# CH32V307VCT6-R0.net
KiCad netlist of a schematic drawn in Altium Designer
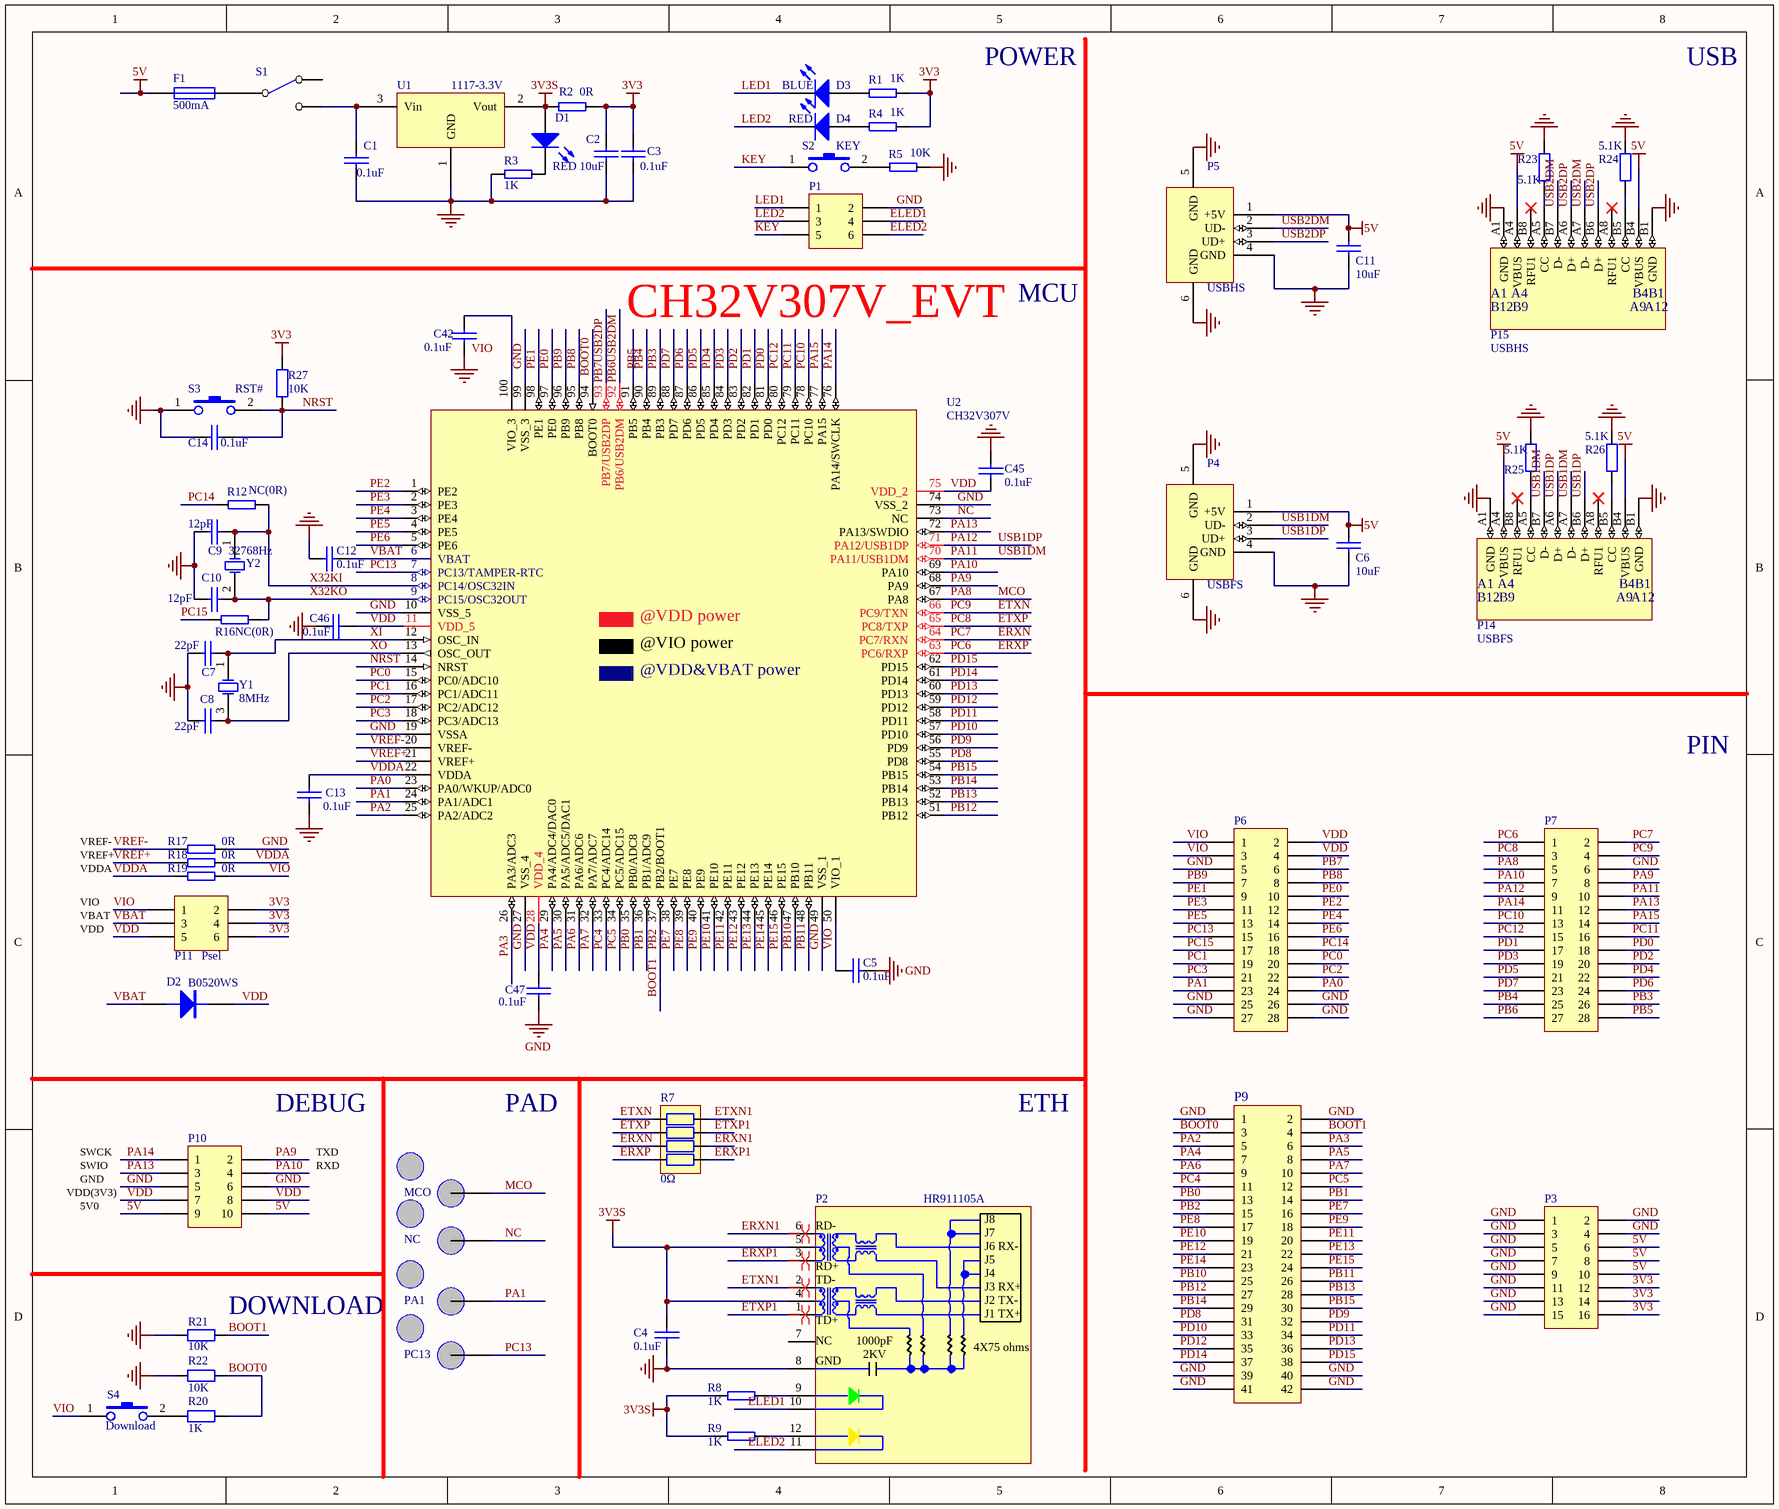
[diagram p0: CH32V307VCT6-R0.SchDoc]

(export (version "E")
  (design (tool "Eeschema 10.0.6"))
  (components
    (comp (ref "C1")
      (value "0.1uF")
      (footprint "0603_C")
      (description "Capacitor")
      (libsource (lib "") (part "CAP_1"))
    )
    (comp (ref "C2")
      (value "10uF")
      (footprint "3216_C")
      (description "Capacitor")
      (libsource (lib "") (part "CAP_1"))
    )
    (comp (ref "C3")
      (value "0.1uF")
      (footprint "0603_C")
      (description "Capacitor")
      (libsource (lib "") (part "CAP_1"))
    )
    (comp (ref "C4")
      (value "0.1uF")
      (footprint "0603_C")
      (description "Capacitor")
      (libsource (lib "") (part "CAP_1"))
    )
    (comp (ref "C5")
      (value "0.1uF")
      (footprint "0603_C")
      (description "Capacitor")
      (libsource (lib "") (part "CAP_1"))
    )
    (comp (ref "C6")
      (value "10uF")
      (footprint "3216_C")
      (description "Capacitor")
      (libsource (lib "*") (part "CAP"))
    )
    (comp (ref "C7")
      (value "22pF")
      (footprint "0603_C")
      (description "Capacitor")
      (libsource (lib "") (part "CAP_1"))
    )
    (comp (ref "C8")
      (value "22pF")
      (footprint "0603_C")
      (description "Capacitor")
      (libsource (lib "") (part "CAP_1"))
    )
    (comp (ref "C9")
      (value "12pF")
      (footprint "0603_C")
      (description "Capacitor")
      (libsource (lib "") (part "CAP_1"))
    )
    (comp (ref "C10")
      (value "12pF")
      (footprint "0603_C")
      (description "Capacitor")
      (libsource (lib "") (part "CAP_1"))
    )
    (comp (ref "C11")
      (value "10uF")
      (footprint "3216_C")
      (description "Capacitor")
      (libsource (lib "*") (part "CAP"))
    )
    (comp (ref "C12")
      (value "0.1uF")
      (footprint "0603_C")
      (description "Capacitor")
      (libsource (lib "") (part "CAP_1"))
    )
    (comp (ref "C13")
      (value "0.1uF")
      (footprint "0603_C")
      (description "Capacitor")
      (libsource (lib "") (part "CAP_1"))
    )
    (comp (ref "C14")
      (value "0.1uF")
      (footprint "0603_C")
      (description "Capacitor")
      (libsource (lib "*") (part "CAP"))
    )
    (comp (ref "C42")
      (value "0.1uF")
      (footprint "0603_C")
      (description "Capacitor")
      (libsource (lib "") (part "CAP_1"))
    )
    (comp (ref "C45")
      (value "0.1uF")
      (footprint "0603_C")
      (description "Capacitor")
      (libsource (lib "") (part "CAP_1"))
    )
    (comp (ref "C46")
      (value "0.1uF")
      (footprint "0603_C")
      (description "Capacitor")
      (libsource (lib "") (part "CAP_1"))
    )
    (comp (ref "C47")
      (value "0.1uF")
      (footprint "0603_C")
      (description "Capacitor")
      (libsource (lib "") (part "CAP_1"))
    )
    (comp (ref "D1")
      (value "RED")
      (footprint "0603+")
      (description "Typical INFRARED GaAs LED")
      (fields (field (name "PUBLISHER") "Altium Limited"))
      (libsource (lib "*") (part "LED0"))
    )
    (comp (ref "D2")
      (value "B0520WS")
      (footprint "SOD-323")
      (description "Diode")
      (libsource (lib "*") (part "DIODE"))
    )
    (comp (ref "D3")
      (value "BLUE")
      (footprint "0603+")
      (description "Typical INFRARED GaAs LED")
      (fields (field (name "PUBLISHER") "Altium Limited"))
      (libsource (lib "*") (part "LED0"))
    )
    (comp (ref "D4")
      (value "RED")
      (footprint "0603+")
      (description "Typical INFRARED GaAs LED")
      (fields (field (name "PUBLISHER") "Altium Limited"))
      (libsource (lib "*") (part "LED0"))
    )
    (comp (ref "F1")
      (value "500mA")
      (footprint "0805")
      (description "Fuse")
      (libsource (lib "wch_sch_others") (part "FUSE1"))
    )
    (comp (ref "MCO")
      (value "Testpoint")
      (footprint "TESTPOINT1")
      (description "测试点")
      (libsource (lib "wch_sch_others") (part "Testpoint"))
    )
    (comp (ref "NC")
      (value "Testpoint")
      (footprint "TESTPOINT1")
      (description "测试点")
      (libsource (lib "wch_sch_others") (part "Testpoint"))
    )
    (comp (ref "P1")
      (value "IO")
      (footprint "IDC6-2.54mm")
      (description "Header, 3-Pin, Dual row, Right Angle")
      (fields (field (name "PUBLISHER") "Altium Limited"))
      (libsource (lib "Miscellaneous Connectors") (part "Header 3X2H"))
    )
    (comp (ref "P2") (value "HR911105A") (footprint "HR911105A") (libsource (lib "*") (part "HR911105A")))
    (comp (ref "P3")
      (value "Ppin")
      (footprint "IDC16-2.54mm")
      (description "Header, 8-Pin, Dual row, Right Angle")
      (fields (field (name "PUBLISHER") "Altium Limited"))
      (libsource (lib "Miscellaneous Connectors") (part "Header 8X2H"))
    )
    (comp (ref "P4")
      (value "USBFS")
      (footprint "USBAF")
      (description "USB Port")
      (libsource (lib "*") (part "USB"))
    )
    (comp (ref "P5")
      (value "USBHS")
      (footprint "USBAF")
      (description "USB Port")
      (libsource (lib "*") (part "USB"))
    )
    (comp (ref "P6")
      (value "HEADER 14x2")
      (footprint "MYPCB:IDC28-2.54MM")
      (description "Header, 14-Pin, Dual row")
      (libsource (lib "wch_sch_others") (part "HEADER 14x2"))
    )
    (comp (ref "P7")
      (value "HEADER 14x2")
      (footprint "MYPCB:IDC28-2.54MM")
      (description "Header, 14-Pin, Dual row")
      (libsource (lib "wch_sch_others") (part "HEADER 14x2"))
    )
    (comp (ref "P9")
      (value "HEADER 21x2")
      (footprint "MYPCB:IDC42-2.54MM")
      (description "Header, 21-Pin, Dual row")
      (libsource (lib "wch_sch_others") (part "HEADER 21x2"))
    )
    (comp (ref "P10")
      (value "LINK")
      (footprint "IDC10-2.54mm")
      (description "Header, 5-Pin, Dual row, Right Angle")
      (fields (field (name "PUBLISHER") "Altium Limited"))
      (libsource (lib "Miscellaneous Connectors") (part "Header 5X2H"))
    )
    (comp (ref "P11")
      (value "Psel")
      (footprint "IDC6-2.54mm")
      (description "Header, 3-Pin, Dual row, Right Angle")
      (fields (field (name "PUBLISHER") "Altium Limited"))
      (libsource (lib "Miscellaneous Connectors") (part "Header 3X2H"))
    )
    (comp (ref "P14")
      (value "USBFS")
      (footprint "TYPE-C-Receptacle-2.0")
      (libsource (lib "*") (part "TYPE-C1"))
    )
    (comp (ref "P15")
      (value "USBHS")
      (footprint "TYPE-C-Receptacle-2.0")
      (libsource (lib "*") (part "TYPE-C1"))
    )
    (comp (ref "PA1")
      (value "Testpoint")
      (footprint "TESTPOINT1")
      (description "测试点")
      (libsource (lib "wch_sch_others") (part "Testpoint"))
    )
    (comp (ref "PC13")
      (value "Testpoint")
      (footprint "TESTPOINT1")
      (description "测试点")
      (libsource (lib "wch_sch_others") (part "Testpoint"))
    )
    (comp (ref "R1") (value "1K") (footprint "0603") (libsource (lib "wch_sch_others") (part "RES")))
    (comp (ref "R2") (value "0R") (footprint "0603") (libsource (lib "wch_sch_others") (part "RES")))
    (comp (ref "R3") (value "1K") (footprint "0603") (libsource (lib "wch_sch_others") (part "RES")))
    (comp (ref "R4") (value "1K") (footprint "0603") (libsource (lib "wch_sch_others") (part "RES")))
    (comp (ref "R5") (value "10K") (footprint "0603") (libsource (lib "wch_sch_others") (part "RES")))
    (comp (ref "R7")
      (value "0Ω")
      (footprint "RCA-8P4R-0603")
      (description "贴片网络排阻")
      (fields (field (name "版权归属") "源创客"))
      (libsource (lib "wch_sch_others") (part "R-8P4R"))
    )
    (comp (ref "R8") (value "1K") (footprint "0603") (libsource (lib "wch_sch_others") (part "RES")))
    (comp (ref "R9") (value "1K") (footprint "0603") (libsource (lib "wch_sch_others") (part "RES")))
    (comp (ref "R12") (value "NC(0R)") (footprint "0603") (libsource (lib "wch_sch_others") (part "RES")))
    (comp (ref "R16") (value "NC(0R)") (footprint "0603") (libsource (lib "wch_sch_others") (part "RES")))
    (comp (ref "R17") (value "0R") (footprint "0603") (libsource (lib "*") (part "R")))
    (comp (ref "R18") (value "0R") (footprint "0603") (libsource (lib "*") (part "R")))
    (comp (ref "R19") (value "0R") (footprint "0603") (libsource (lib "*") (part "R")))
    (comp (ref "R20")
      (value "1K")
      (footprint "0603")
      (description "Resistor")
      (fields (field (name "PUBLISHER") "Altium Limited"))
      (libsource (lib "Miscellaneous Devices") (part "Res2"))
    )
    (comp (ref "R21")
      (value "10K")
      (footprint "0603")
      (description "Resistor")
      (fields (field (name "PUBLISHER") "Altium Limited"))
      (libsource (lib "Miscellaneous Devices") (part "Res2"))
    )
    (comp (ref "R22")
      (value "10K")
      (footprint "0603")
      (description "Resistor")
      (fields (field (name "PUBLISHER") "Altium Limited"))
      (libsource (lib "Miscellaneous Devices") (part "Res2"))
    )
    (comp (ref "R23")
      (value "5.1K")
      (footprint "0603")
      (description "Resistor")
      (libsource (lib "") (part "Res2_1"))
    )
    (comp (ref "R24")
      (value "5.1K")
      (footprint "0603")
      (description "Resistor")
      (libsource (lib "") (part "Res2_1"))
    )
    (comp (ref "R25")
      (value "5.1K")
      (footprint "0603")
      (description "Resistor")
      (libsource (lib "") (part "Res2_1"))
    )
    (comp (ref "R26")
      (value "5.1K")
      (footprint "0603")
      (description "Resistor")
      (libsource (lib "") (part "Res2_1"))
    )
    (comp (ref "R27")
      (value "10K")
      (footprint "0603")
      (description "Resistor")
      (fields (field (name "PUBLISHER") "Altium Limited"))
      (libsource (lib "") (part "Res2_1"))
    )
    (comp (ref "S1") (value "SW SPDT") (footprint "KEY_B") (libsource (lib "*") (part "SW SPDT")))
    (comp (ref "S2")
      (value "KEY")
      (footprint "SMD_6.1x3.65x2.5mm-KEY")
      (libsource (lib "wch_sch_others") (part "KEY1"))
    )
    (comp (ref "S3")
      (value "RST#")
      (footprint "SMD_6.1x3.65x2.5mm-KEY")
      (libsource (lib "wch_sch_others") (part "KEY1"))
    )
    (comp (ref "S4")
      (value "Download")
      (footprint "SMD_6.1x3.65x2.5mm-KEY")
      (libsource (lib "wch_sch_others") (part "KEY1"))
    )
    (comp (ref "U1")
      (value "1117-3.3V")
      (footprint "SOT-223")
      (libsource (lib "wch_sch_others") (part "1117-3.3V"))
    )
    (comp (ref "U2")
      (value "CH32V307V")
      (footprint "LQFP100")
      (description "RISC-V FPU HD-MCU, 144MHz, USB_480M, USB OTG, 1000M Ethernet MAC, 2*CAN, FSMC+DVP")
      (libsource (lib "CHXXX") (part "CH32V307V"))
    )
    (comp (ref "Y1")
      (value "8MHz")
      (footprint "XT3225")
      (description "Crystal Oscillator")
      (fields (field (name "PUBLISHER") "Altium Limited"))
      (libsource (lib "*") (part "XTAL"))
    )
    (comp (ref "Y2")
      (value "32768Hz")
      (footprint "FC-135")
      (description "Crystal Oscillator")
      (fields (field (name "PUBLISHER") "Altium Limited"))
      (libsource (lib "") (part "XTAL_1"))
    )
  )
  (nets
    (net (code "2") (name "/BOOT0") (class "Default")
      (node (ref "P9") (pin "3") (pinfunction "3_3") (pintype "passive"))
      (node (ref "R20") (pin "1") (pinfunction "1_1") (pintype "passive"))
      (node (ref "R22") (pin "1") (pinfunction "1_1") (pintype "passive"))
      (node (ref "U2") (pin "94") (pinfunction "BOOT0_94") (pintype "input"))
    )
    (net (code "3") (name "/BOOT1") (class "Default")
      (node (ref "P9") (pin "15") (pinfunction "15_15") (pintype "passive"))
      (node (ref "P9") (pin "4") (pinfunction "4_4") (pintype "passive"))
      (node (ref "R21") (pin "1") (pinfunction "1_1") (pintype "passive"))
      (node (ref "U2") (pin "37") (pinfunction "PB2/BOOT1_37") (pintype "bidirectional"))
    )
    (net (code "4") (name "/ELED1") (class "Default")
      (node (ref "P1") (pin "4") (pinfunction "4_4") (pintype "passive"))
      (node (ref "P2") (pin "10") (pintype "passive"))
    )
    (net (code "5") (name "/ELED2") (class "Default")
      (node (ref "P1") (pin "6") (pinfunction "6_6") (pintype "passive"))
      (node (ref "P2") (pin "11") (pintype "passive"))
    )
    (net (code "6") (name "/ERXN") (class "Default")
      (node (ref "P7") (pin "2") (pinfunction "2_2") (pintype "passive"))
      (node (ref "R7") (pin "3") (pinfunction "3_3") (pintype "passive"))
      (node (ref "U2") (pin "64") (pinfunction "PC7/RXN_64") (pintype "bidirectional"))
    )
    (net (code "7") (name "/ERXN1") (class "Default")
      (node (ref "P2") (pin "6") (pintype "passive"))
      (node (ref "R7") (pin "6") (pinfunction "6_6") (pintype "passive"))
    )
    (net (code "8") (name "/ERXP") (class "Default")
      (node (ref "P7") (pin "1") (pinfunction "1_1") (pintype "passive"))
      (node (ref "R7") (pin "4") (pinfunction "4_4") (pintype "passive"))
      (node (ref "U2") (pin "63") (pinfunction "PC6/RXP_63") (pintype "bidirectional"))
    )
    (net (code "9") (name "/ERXP1") (class "Default")
      (node (ref "P2") (pin "3") (pintype "passive"))
      (node (ref "R7") (pin "5") (pinfunction "5_5") (pintype "passive"))
    )
    (net (code "10") (name "/ETXN") (class "Default")
      (node (ref "P7") (pin "4") (pinfunction "4_4") (pintype "passive"))
      (node (ref "R7") (pin "1") (pinfunction "1_1") (pintype "passive"))
      (node (ref "U2") (pin "66") (pinfunction "PC9/TXN_66") (pintype "bidirectional"))
    )
    (net (code "11") (name "/ETXN1") (class "Default")
      (node (ref "P2") (pin "2") (pintype "passive"))
      (node (ref "R7") (pin "8") (pinfunction "8_8") (pintype "passive"))
    )
    (net (code "12") (name "/ETXP") (class "Default")
      (node (ref "P7") (pin "3") (pinfunction "3_3") (pintype "passive"))
      (node (ref "R7") (pin "2") (pinfunction "2_2") (pintype "passive"))
      (node (ref "U2") (pin "65") (pinfunction "PC8/TXP_65") (pintype "bidirectional"))
    )
    (net (code "13") (name "/ETXP1") (class "Default")
      (node (ref "P2") (pin "1") (pintype "passive"))
      (node (ref "R7") (pin "7") (pinfunction "7_7") (pintype "passive"))
    )
    (net (code "14") (name "/KEY") (class "Default")
      (node (ref "P1") (pin "5") (pinfunction "5_5") (pintype "passive"))
      (node (ref "S2") (pin "1") (pinfunction "1_1") (pintype "passive"))
    )
    (net (code "15") (name "/LED1") (class "Default")
      (node (ref "D3") (pin "2") (pinfunction "K_2") (pintype "passive"))
      (node (ref "P1") (pin "1") (pinfunction "1_1") (pintype "passive"))
    )
    (net (code "16") (name "/LED2") (class "Default")
      (node (ref "D4") (pin "2") (pinfunction "K_2") (pintype "passive"))
      (node (ref "P1") (pin "3") (pinfunction "3_3") (pintype "passive"))
    )
    (net (code "17") (name "/MCO") (class "Default")
      (node (ref "MCO") (pin "1") (pinfunction "point_1") (pintype "passive"))
      (node (ref "P7") (pin "5") (pinfunction "5_5") (pintype "passive"))
      (node (ref "U2") (pin "67") (pinfunction "PA8_67") (pintype "bidirectional"))
    )
    (net (code "18") (name "/NC") (class "Default")
      (node (ref "NC") (pin "1") (pinfunction "point_1") (pintype "passive"))
      (node (ref "U2") (pin "73") (pinfunction "NC_73") (pintype "tri_state"))
    )
    (net (code "19") (name "/NRST") (class "Default")
      (node (ref "C14") (pin "2") (pinfunction "2_2") (pintype "passive"))
      (node (ref "R27") (pin "1") (pinfunction "1_1") (pintype "passive"))
      (node (ref "S3") (pin "2") (pinfunction "2_2") (pintype "passive"))
      (node (ref "U2") (pin "14") (pinfunction "NRST_14") (pintype "input"))
    )
    (net (code "20") (name "/PA0") (class "Default")
      (node (ref "P6") (pin "24") (pinfunction "24_24") (pintype "passive"))
      (node (ref "U2") (pin "23") (pinfunction "PA0/WKUP/ADC0_23") (pintype "bidirectional"))
    )
    (net (code "21") (name "/PA1") (class "Default")
      (node (ref "P6") (pin "23") (pinfunction "23_23") (pintype "passive"))
      (node (ref "PA1") (pin "1") (pinfunction "point_1") (pintype "passive"))
      (node (ref "U2") (pin "24") (pinfunction "PA1/ADC1_24") (pintype "bidirectional"))
    )
    (net (code "22") (name "/PA2") (class "Default")
      (node (ref "P9") (pin "5") (pinfunction "5_5") (pintype "passive"))
      (node (ref "U2") (pin "25") (pinfunction "PA2/ADC2_25") (pintype "bidirectional"))
    )
    (net (code "23") (name "/PA3") (class "Default")
      (node (ref "P9") (pin "6") (pinfunction "6_6") (pintype "passive"))
      (node (ref "U2") (pin "26") (pinfunction "PA3/ADC3_26") (pintype "bidirectional"))
    )
    (net (code "24") (name "/PA4") (class "Default")
      (node (ref "P9") (pin "7") (pinfunction "7_7") (pintype "passive"))
      (node (ref "U2") (pin "29") (pinfunction "PA4/ADC4/DAC0_29") (pintype "bidirectional"))
    )
    (net (code "25") (name "/PA5") (class "Default")
      (node (ref "P9") (pin "8") (pinfunction "8_8") (pintype "passive"))
      (node (ref "U2") (pin "30") (pinfunction "PA5/ADC5/DAC1_30") (pintype "bidirectional"))
    )
    (net (code "26") (name "/PA6") (class "Default")
      (node (ref "P9") (pin "9") (pinfunction "9_9") (pintype "passive"))
      (node (ref "U2") (pin "31") (pinfunction "PA6/ADC6_31") (pintype "bidirectional"))
    )
    (net (code "27") (name "/PA7") (class "Default")
      (node (ref "P9") (pin "10") (pinfunction "10_10") (pintype "passive"))
      (node (ref "U2") (pin "32") (pinfunction "PA7/ADC7_32") (pintype "bidirectional"))
    )
    (net (code "28") (name "/PA9") (class "Default")
      (node (ref "P10") (pin "2") (pinfunction "2_2") (pintype "passive"))
      (node (ref "P7") (pin "8") (pinfunction "8_8") (pintype "passive"))
      (node (ref "U2") (pin "68") (pinfunction "PA9_68") (pintype "bidirectional"))
    )
    (net (code "29") (name "/PA10") (class "Default")
      (node (ref "P10") (pin "4") (pinfunction "4_4") (pintype "passive"))
      (node (ref "P7") (pin "7") (pinfunction "7_7") (pintype "passive"))
      (node (ref "U2") (pin "69") (pinfunction "PA10_69") (pintype "bidirectional"))
    )
    (net (code "30") (name "/PA11") (class "Default")
      (node (ref "P14") (pin "A7") (pinfunction "D-_A7") (pintype "bidirectional"))
      (node (ref "P14") (pin "B7") (pinfunction "D-_B7") (pintype "bidirectional"))
      (node (ref "P4") (pin "2") (pinfunction "UD-_2") (pintype "bidirectional"))
      (node (ref "P7") (pin "10") (pinfunction "10_10") (pintype "passive"))
      (node (ref "U2") (pin "70") (pinfunction "PA11/USB1DM_70") (pintype "bidirectional"))
    )
    (net (code "31") (name "/PA12") (class "Default")
      (node (ref "P14") (pin "A6") (pinfunction "D+_A6") (pintype "bidirectional"))
      (node (ref "P14") (pin "B6") (pinfunction "D+_B6") (pintype "bidirectional"))
      (node (ref "P4") (pin "3") (pinfunction "UD+_3") (pintype "bidirectional"))
      (node (ref "P7") (pin "9") (pinfunction "9_9") (pintype "passive"))
      (node (ref "U2") (pin "71") (pinfunction "PA12/USB1DP_71") (pintype "bidirectional"))
    )
    (net (code "32") (name "/PA13") (class "Default")
      (node (ref "P10") (pin "3") (pinfunction "3_3") (pintype "passive"))
      (node (ref "P7") (pin "12") (pinfunction "12_12") (pintype "passive"))
      (node (ref "U2") (pin "72") (pinfunction "PA13/SWDIO_72") (pintype "bidirectional"))
    )
    (net (code "33") (name "/PA14") (class "Default")
      (node (ref "P10") (pin "1") (pinfunction "1_1") (pintype "passive"))
      (node (ref "P7") (pin "11") (pinfunction "11_11") (pintype "passive"))
      (node (ref "U2") (pin "76") (pinfunction "PA14/SWCLK_76") (pintype "bidirectional"))
    )
    (net (code "34") (name "/PA15") (class "Default")
      (node (ref "P7") (pin "14") (pinfunction "14_14") (pintype "passive"))
      (node (ref "U2") (pin "77") (pinfunction "PA15_77") (pintype "bidirectional"))
    )
    (net (code "35") (name "/PB0") (class "Default")
      (node (ref "P9") (pin "13") (pinfunction "13_13") (pintype "passive"))
      (node (ref "U2") (pin "35") (pinfunction "PB0/ADC8_35") (pintype "bidirectional"))
    )
    (net (code "36") (name "/PB1") (class "Default")
      (node (ref "P9") (pin "14") (pinfunction "14_14") (pintype "passive"))
      (node (ref "U2") (pin "36") (pinfunction "PB1/ADC9_36") (pintype "bidirectional"))
    )
    (net (code "37") (name "/PB3") (class "Default")
      (node (ref "P7") (pin "26") (pinfunction "26_26") (pintype "passive"))
      (node (ref "U2") (pin "89") (pinfunction "PB3_89") (pintype "bidirectional"))
    )
    (net (code "38") (name "/PB4") (class "Default")
      (node (ref "P7") (pin "25") (pinfunction "25_25") (pintype "passive"))
      (node (ref "U2") (pin "90") (pinfunction "PB4_90") (pintype "bidirectional"))
    )
    (net (code "39") (name "/PB5") (class "Default")
      (node (ref "P7") (pin "28") (pinfunction "28_28") (pintype "passive"))
    )
    (net (code "40") (name "/PB6") (class "Default")
      (node (ref "P15") (pin "A7") (pinfunction "D-_A7") (pintype "bidirectional"))
      (node (ref "P15") (pin "B7") (pinfunction "D-_B7") (pintype "bidirectional"))
      (node (ref "P5") (pin "2") (pinfunction "UD-_2") (pintype "bidirectional"))
      (node (ref "P7") (pin "27") (pinfunction "27_27") (pintype "passive"))
      (node (ref "U2") (pin "92") (pinfunction "PB6/USB2DM_92") (pintype "bidirectional"))
    )
    (net (code "41") (name "/PB7") (class "Default")
      (node (ref "P15") (pin "A6") (pinfunction "D+_A6") (pintype "bidirectional"))
      (node (ref "P15") (pin "B6") (pinfunction "D+_B6") (pintype "bidirectional"))
      (node (ref "P5") (pin "3") (pinfunction "UD+_3") (pintype "bidirectional"))
      (node (ref "P6") (pin "6") (pinfunction "6_6") (pintype "passive"))
      (node (ref "U2") (pin "93") (pinfunction "PB7/USB2DP_93") (pintype "bidirectional"))
    )
    (net (code "42") (name "/PB8") (class "Default")
      (node (ref "P6") (pin "8") (pinfunction "8_8") (pintype "passive"))
      (node (ref "U2") (pin "95") (pinfunction "PB8_95") (pintype "bidirectional"))
    )
    (net (code "43") (name "/PB9") (class "Default")
      (node (ref "P6") (pin "7") (pinfunction "7_7") (pintype "passive"))
      (node (ref "U2") (pin "96") (pinfunction "PB9_96") (pintype "bidirectional"))
    )
    (net (code "44") (name "/PB10") (class "Default")
      (node (ref "P9") (pin "25") (pinfunction "25_25") (pintype "passive"))
      (node (ref "U2") (pin "47") (pinfunction "PB10_47") (pintype "bidirectional"))
    )
    (net (code "45") (name "/PB11") (class "Default")
      (node (ref "P9") (pin "26") (pinfunction "26_26") (pintype "passive"))
      (node (ref "U2") (pin "48") (pinfunction "PB11_48") (pintype "bidirectional"))
    )
    (net (code "46") (name "/PB12") (class "Default")
      (node (ref "P9") (pin "27") (pinfunction "27_27") (pintype "passive"))
      (node (ref "U2") (pin "51") (pinfunction "PB12_51") (pintype "bidirectional"))
    )
    (net (code "47") (name "/PB13") (class "Default")
      (node (ref "P9") (pin "28") (pinfunction "28_28") (pintype "passive"))
      (node (ref "U2") (pin "52") (pinfunction "PB13_52") (pintype "bidirectional"))
    )
    (net (code "48") (name "/PB14") (class "Default")
      (node (ref "P9") (pin "29") (pinfunction "29_29") (pintype "passive"))
      (node (ref "U2") (pin "53") (pinfunction "PB14_53") (pintype "bidirectional"))
    )
    (net (code "49") (name "/PB15") (class "Default")
      (node (ref "P9") (pin "30") (pinfunction "30_30") (pintype "passive"))
      (node (ref "U2") (pin "54") (pinfunction "PB15_54") (pintype "bidirectional"))
    )
    (net (code "50") (name "/PC0") (class "Default")
      (node (ref "P6") (pin "20") (pinfunction "20_20") (pintype "passive"))
      (node (ref "U2") (pin "15") (pinfunction "PC0/ADC10_15") (pintype "bidirectional"))
    )
    (net (code "51") (name "/PC1") (class "Default")
      (node (ref "P6") (pin "19") (pinfunction "19_19") (pintype "passive"))
      (node (ref "U2") (pin "16") (pinfunction "PC1/ADC11_16") (pintype "bidirectional"))
    )
    (net (code "52") (name "/PC2") (class "Default")
      (node (ref "P6") (pin "22") (pinfunction "22_22") (pintype "passive"))
      (node (ref "U2") (pin "17") (pinfunction "PC2/ADC12_17") (pintype "bidirectional"))
    )
    (net (code "53") (name "/PC3") (class "Default")
      (node (ref "P6") (pin "21") (pinfunction "21_21") (pintype "passive"))
      (node (ref "U2") (pin "18") (pinfunction "PC3/ADC13_18") (pintype "bidirectional"))
    )
    (net (code "54") (name "/PC4") (class "Default")
      (node (ref "P9") (pin "11") (pinfunction "11_11") (pintype "passive"))
      (node (ref "U2") (pin "33") (pinfunction "PC4/ADC14_33") (pintype "bidirectional"))
    )
    (net (code "55") (name "/PC5") (class "Default")
      (node (ref "P9") (pin "12") (pinfunction "12_12") (pintype "passive"))
      (node (ref "U2") (pin "34") (pinfunction "PC5/ADC15_34") (pintype "bidirectional"))
    )
    (net (code "56") (name "/PC10") (class "Default")
      (node (ref "P7") (pin "13") (pinfunction "13_13") (pintype "passive"))
      (node (ref "U2") (pin "78") (pinfunction "PC10_78") (pintype "bidirectional"))
    )
    (net (code "57") (name "/PC11") (class "Default")
      (node (ref "P7") (pin "16") (pinfunction "16_16") (pintype "passive"))
      (node (ref "U2") (pin "79") (pinfunction "PC11_79") (pintype "bidirectional"))
    )
    (net (code "58") (name "/PC12") (class "Default")
      (node (ref "P7") (pin "15") (pinfunction "15_15") (pintype "passive"))
      (node (ref "U2") (pin "80") (pinfunction "PC12_80") (pintype "bidirectional"))
    )
    (net (code "59") (name "/PC13") (class "Default")
      (node (ref "P6") (pin "15") (pinfunction "15_15") (pintype "passive"))
      (node (ref "PC13") (pin "1") (pinfunction "point_1") (pintype "passive"))
      (node (ref "U2") (pin "7") (pinfunction "PC13/TAMPER-RTC_7") (pintype "bidirectional"))
    )
    (net (code "60") (name "/PC14") (class "Default")
      (node (ref "P6") (pin "18") (pinfunction "18_18") (pintype "passive"))
      (node (ref "R12") (pin "1") (pintype "passive"))
    )
    (net (code "61") (name "/PC15") (class "Default")
      (node (ref "P6") (pin "17") (pinfunction "17_17") (pintype "passive"))
      (node (ref "R16") (pin "1") (pintype "passive"))
    )
    (net (code "62") (name "/PD0") (class "Default")
      (node (ref "P7") (pin "18") (pinfunction "18_18") (pintype "passive"))
      (node (ref "U2") (pin "81") (pinfunction "PD0_81") (pintype "bidirectional"))
    )
    (net (code "63") (name "/PD1") (class "Default")
      (node (ref "P7") (pin "17") (pinfunction "17_17") (pintype "passive"))
      (node (ref "U2") (pin "82") (pinfunction "PD1_82") (pintype "bidirectional"))
    )
    (net (code "64") (name "/PD2") (class "Default")
      (node (ref "P7") (pin "20") (pinfunction "20_20") (pintype "passive"))
      (node (ref "U2") (pin "83") (pinfunction "PD2_83") (pintype "bidirectional"))
    )
    (net (code "65") (name "/PD3") (class "Default")
      (node (ref "P7") (pin "19") (pinfunction "19_19") (pintype "passive"))
      (node (ref "U2") (pin "84") (pinfunction "PD3_84") (pintype "bidirectional"))
    )
    (net (code "66") (name "/PD4") (class "Default")
      (node (ref "P7") (pin "22") (pinfunction "22_22") (pintype "passive"))
      (node (ref "U2") (pin "85") (pinfunction "PD4_85") (pintype "bidirectional"))
    )
    (net (code "67") (name "/PD5") (class "Default")
      (node (ref "P7") (pin "21") (pinfunction "21_21") (pintype "passive"))
      (node (ref "U2") (pin "86") (pinfunction "PD5_86") (pintype "bidirectional"))
    )
    (net (code "68") (name "/PD6") (class "Default")
      (node (ref "P7") (pin "24") (pinfunction "24_24") (pintype "passive"))
      (node (ref "U2") (pin "87") (pinfunction "PD6_87") (pintype "bidirectional"))
    )
    (net (code "69") (name "/PD7") (class "Default")
      (node (ref "P7") (pin "23") (pinfunction "23_23") (pintype "passive"))
      (node (ref "U2") (pin "88") (pinfunction "PD7_88") (pintype "bidirectional"))
    )
    (net (code "70") (name "/PD8") (class "Default")
      (node (ref "P9") (pin "31") (pinfunction "31_31") (pintype "passive"))
      (node (ref "U2") (pin "55") (pinfunction "PD8_55") (pintype "bidirectional"))
    )
    (net (code "71") (name "/PD9") (class "Default")
      (node (ref "P9") (pin "32") (pinfunction "32_32") (pintype "passive"))
      (node (ref "U2") (pin "56") (pinfunction "PD9_56") (pintype "bidirectional"))
    )
    (net (code "72") (name "/PD10") (class "Default")
      (node (ref "P9") (pin "33") (pinfunction "33_33") (pintype "passive"))
      (node (ref "U2") (pin "57") (pinfunction "PD10_57") (pintype "bidirectional"))
    )
    (net (code "73") (name "/PD11") (class "Default")
      (node (ref "P9") (pin "34") (pinfunction "34_34") (pintype "passive"))
      (node (ref "U2") (pin "58") (pinfunction "PD11_58") (pintype "bidirectional"))
    )
    (net (code "74") (name "/PD12") (class "Default")
      (node (ref "P9") (pin "35") (pinfunction "35_35") (pintype "passive"))
      (node (ref "U2") (pin "59") (pinfunction "PD12_59") (pintype "bidirectional"))
    )
    (net (code "75") (name "/PD13") (class "Default")
      (node (ref "P9") (pin "36") (pinfunction "36_36") (pintype "passive"))
      (node (ref "U2") (pin "60") (pinfunction "PD13_60") (pintype "bidirectional"))
    )
    (net (code "76") (name "/PD14") (class "Default")
      (node (ref "P9") (pin "37") (pinfunction "37_37") (pintype "passive"))
      (node (ref "U2") (pin "61") (pinfunction "PD14_61") (pintype "bidirectional"))
    )
    (net (code "77") (name "/PD15") (class "Default")
      (node (ref "P9") (pin "38") (pinfunction "38_38") (pintype "passive"))
      (node (ref "U2") (pin "62") (pinfunction "PD15_62") (pintype "bidirectional"))
    )
    (net (code "78") (name "/PE0") (class "Default")
      (node (ref "P6") (pin "10") (pinfunction "10_10") (pintype "passive"))
      (node (ref "U2") (pin "97") (pinfunction "PE0_97") (pintype "bidirectional"))
    )
    (net (code "79") (name "/PE1") (class "Default")
      (node (ref "P6") (pin "9") (pinfunction "9_9") (pintype "passive"))
      (node (ref "U2") (pin "98") (pinfunction "PE1_98") (pintype "bidirectional"))
    )
    (net (code "80") (name "/PE2") (class "Default")
      (node (ref "P6") (pin "12") (pinfunction "12_12") (pintype "passive"))
      (node (ref "U2") (pin "1") (pinfunction "PE2_1") (pintype "bidirectional"))
    )
    (net (code "81") (name "/PE3") (class "Default")
      (node (ref "P6") (pin "11") (pinfunction "11_11") (pintype "passive"))
      (node (ref "U2") (pin "2") (pinfunction "PE3_2") (pintype "bidirectional"))
    )
    (net (code "82") (name "/PE4") (class "Default")
      (node (ref "P6") (pin "14") (pinfunction "14_14") (pintype "passive"))
      (node (ref "U2") (pin "3") (pinfunction "PE4_3") (pintype "bidirectional"))
    )
    (net (code "83") (name "/PE5") (class "Default")
      (node (ref "P6") (pin "13") (pinfunction "13_13") (pintype "passive"))
      (node (ref "U2") (pin "4") (pinfunction "PE5_4") (pintype "bidirectional"))
    )
    (net (code "84") (name "/PE6") (class "Default")
      (node (ref "P6") (pin "16") (pinfunction "16_16") (pintype "passive"))
      (node (ref "U2") (pin "5") (pinfunction "PE6_5") (pintype "bidirectional"))
    )
    (net (code "85") (name "/PE7") (class "Default")
      (node (ref "P9") (pin "16") (pinfunction "16_16") (pintype "passive"))
      (node (ref "U2") (pin "38") (pinfunction "PE7_38") (pintype "bidirectional"))
    )
    (net (code "86") (name "/PE8") (class "Default")
      (node (ref "P9") (pin "17") (pinfunction "17_17") (pintype "passive"))
      (node (ref "U2") (pin "39") (pinfunction "PE8_39") (pintype "bidirectional"))
    )
    (net (code "87") (name "/PE9") (class "Default")
      (node (ref "P9") (pin "18") (pinfunction "18_18") (pintype "passive"))
      (node (ref "U2") (pin "40") (pinfunction "PE9_40") (pintype "bidirectional"))
    )
    (net (code "88") (name "/PE10") (class "Default")
      (node (ref "P9") (pin "19") (pinfunction "19_19") (pintype "passive"))
      (node (ref "U2") (pin "41") (pinfunction "PE10_41") (pintype "bidirectional"))
    )
    (net (code "89") (name "/PE11") (class "Default")
      (node (ref "P9") (pin "20") (pinfunction "20_20") (pintype "passive"))
      (node (ref "U2") (pin "42") (pinfunction "PE11_42") (pintype "bidirectional"))
    )
    (net (code "90") (name "/PE12") (class "Default")
      (node (ref "P9") (pin "21") (pinfunction "21_21") (pintype "passive"))
      (node (ref "U2") (pin "43") (pinfunction "PE12_43") (pintype "bidirectional"))
    )
    (net (code "91") (name "/PE13") (class "Default")
      (node (ref "P9") (pin "22") (pinfunction "22_22") (pintype "passive"))
      (node (ref "U2") (pin "44") (pinfunction "PE13_44") (pintype "bidirectional"))
    )
    (net (code "92") (name "/PE14") (class "Default")
      (node (ref "P9") (pin "23") (pinfunction "23_23") (pintype "passive"))
      (node (ref "U2") (pin "45") (pinfunction "PE14_45") (pintype "bidirectional"))
    )
    (net (code "93") (name "/PE15") (class "Default")
      (node (ref "P9") (pin "24") (pinfunction "24_24") (pintype "passive"))
      (node (ref "U2") (pin "46") (pinfunction "PE15_46") (pintype "bidirectional"))
    )
    (net (code "94") (name "/VBAT") (class "Default")
      (node (ref "C12") (pin "2") (pinfunction "2_2") (pintype "passive"))
      (node (ref "D2") (pin "1") (pinfunction "A_1") (pintype "passive"))
      (node (ref "P11") (pin "3") (pinfunction "3_3") (pintype "passive"))
      (node (ref "U2") (pin "6") (pinfunction "VBAT_6") (pintype "power_in"))
    )
    (net (code "95") (name "/VDD") (class "Default")
      (node (ref "C45") (pin "1") (pinfunction "1_1") (pintype "passive"))
      (node (ref "C46") (pin "1") (pinfunction "1_1") (pintype "passive"))
      (node (ref "C47") (pin "2") (pinfunction "2_2") (pintype "passive"))
      (node (ref "D2") (pin "2") (pinfunction "K_2") (pintype "passive"))
      (node (ref "P10") (pin "7") (pinfunction "7_7") (pintype "passive"))
      (node (ref "P10") (pin "8") (pinfunction "8_8") (pintype "passive"))
      (node (ref "P11") (pin "5") (pinfunction "5_5") (pintype "passive"))
      (node (ref "P6") (pin "2") (pinfunction "2_2") (pintype "passive"))
      (node (ref "P6") (pin "4") (pinfunction "4_4") (pintype "passive"))
      (node (ref "U2") (pin "11") (pinfunction "VDD_5_11") (pintype "power_in"))
      (node (ref "U2") (pin "28") (pinfunction "VDD_4_28") (pintype "power_in"))
      (node (ref "U2") (pin "75") (pinfunction "VDD_2_75") (pintype "power_in"))
    )
    (net (code "96") (name "/VDDA") (class "Default")
      (node (ref "C13") (pin "1") (pinfunction "1_1") (pintype "passive"))
      (node (ref "R18") (pin "1") (pinfunction "1_1") (pintype "passive"))
      (node (ref "R19") (pin "2") (pinfunction "2_2") (pintype "passive"))
      (node (ref "U2") (pin "22") (pinfunction "VDDA_22") (pintype "power_in"))
    )
    (net (code "97") (name "/VIO") (class "Default")
      (node (ref "C5") (pin "1") (pinfunction "1_1") (pintype "passive"))
      (node (ref "P11") (pin "1") (pinfunction "1_1") (pintype "passive"))
      (node (ref "P6") (pin "1") (pinfunction "1_1") (pintype "passive"))
      (node (ref "P6") (pin "3") (pinfunction "3_3") (pintype "passive"))
      (node (ref "R19") (pin "1") (pinfunction "1_1") (pintype "passive"))
      (node (ref "S4") (pin "1") (pinfunction "1_1") (pintype "passive"))
      (node (ref "U2") (pin "50") (pinfunction "VIO_1_50") (pintype "power_in"))
    )
    (net (code "98") (name "/VREF+") (class "Default")
      (node (ref "R18") (pin "2") (pinfunction "2_2") (pintype "passive"))
      (node (ref "U2") (pin "21") (pinfunction "VREF+_21") (pintype "power_in"))
    )
    (net (code "99") (name "/VREF-") (class "Default")
      (node (ref "R17") (pin "2") (pinfunction "2_2") (pintype "passive"))
      (node (ref "U2") (pin "20") (pinfunction "VREF-_20") (pintype "power_in"))
    )
    (net (code "100") (name "/X32KI") (class "Default")
      (node (ref "C9") (pin "2") (pinfunction "2_2") (pintype "passive"))
      (node (ref "R12") (pin "2") (pintype "passive"))
      (node (ref "U2") (pin "8") (pinfunction "PC14/OSC32IN_8") (pintype "bidirectional"))
      (node (ref "Y2") (pin "1") (pinfunction "OSC1_1") (pintype "passive"))
    )
    (net (code "101") (name "/X32KO") (class "Default")
      (node (ref "C10") (pin "2") (pinfunction "2_2") (pintype "passive"))
      (node (ref "R16") (pin "2") (pintype "passive"))
      (node (ref "U2") (pin "9") (pinfunction "PC15/OSC32OUT_9") (pintype "bidirectional"))
      (node (ref "Y2") (pin "2") (pinfunction "OSC2_2") (pintype "passive"))
    )
    (net (code "102") (name "/XI") (class "Default")
      (node (ref "C7") (pin "2") (pinfunction "2_2") (pintype "passive"))
      (node (ref "U2") (pin "12") (pinfunction "OSC_IN_12") (pintype "input"))
      (node (ref "Y1") (pin "1") (pinfunction "OSC1_1") (pintype "passive"))
    )
    (net (code "103") (name "/XO") (class "Default")
      (node (ref "C8") (pin "2") (pinfunction "2_2") (pintype "passive"))
      (node (ref "U2") (pin "13") (pinfunction "OSC_OUT_13") (pintype "output"))
      (node (ref "Y1") (pin "3") (pinfunction "OSC2_3") (pintype "passive"))
    )
    (net (code "104") (name "3V3") (class "Default")
      (node (ref "C2") (pin "1") (pinfunction "1_1") (pintype "passive"))
      (node (ref "C3") (pin "1") (pinfunction "1_1") (pintype "passive"))
      (node (ref "P11") (pin "2") (pinfunction "2_2") (pintype "passive"))
      (node (ref "P11") (pin "4") (pinfunction "4_4") (pintype "passive"))
      (node (ref "P11") (pin "6") (pinfunction "6_6") (pintype "passive"))
      (node (ref "P3") (pin "12") (pinfunction "12_12") (pintype "passive"))
      (node (ref "P3") (pin "14") (pinfunction "14_14") (pintype "passive"))
      (node (ref "P3") (pin "16") (pinfunction "16_16") (pintype "passive"))
      (node (ref "R1") (pin "1") (pintype "passive"))
      (node (ref "R2") (pin "1") (pintype "passive"))
      (node (ref "R27") (pin "2") (pinfunction "2_2") (pintype "passive"))
      (node (ref "R4") (pin "1") (pintype "passive"))
    )
    (net (code "105") (name "3V3S") (class "Default")
      (node (ref "C4") (pin "2") (pinfunction "2_2") (pintype "passive"))
      (node (ref "D1") (pin "1") (pinfunction "A_1") (pintype "passive"))
      (node (ref "P2") (pin "4") (pintype "passive"))
      (node (ref "P2") (pin "5") (pintype "passive"))
      (node (ref "R2") (pin "2") (pintype "passive"))
      (node (ref "R8") (pin "1") (pintype "passive"))
      (node (ref "R9") (pin "1") (pintype "passive"))
      (node (ref "U1") (pin "2") (pinfunction "Vout_2") (pintype "passive"))
    )
    (net (code "106") (name "5V") (class "Default")
      (node (ref "C11") (pin "1") (pinfunction "1_1") (pintype "passive"))
      (node (ref "C6") (pin "1") (pinfunction "1_1") (pintype "passive"))
      (node (ref "F1") (pin "1") (pinfunction "1_1") (pintype "passive"))
      (node (ref "P10") (pin "10") (pinfunction "10_10") (pintype "passive"))
      (node (ref "P10") (pin "9") (pinfunction "9_9") (pintype "passive"))
      (node (ref "P14") (pin "A4") (pinfunction "VBUS_A4") (pintype "bidirectional"))
      (node (ref "P14") (pin "B4") (pinfunction "VBUS_B4") (pintype "bidirectional"))
      (node (ref "P15") (pin "A4") (pinfunction "VBUS_A4") (pintype "bidirectional"))
      (node (ref "P15") (pin "B4") (pinfunction "VBUS_B4") (pintype "bidirectional"))
      (node (ref "P3") (pin "10") (pinfunction "10_10") (pintype "passive"))
      (node (ref "P3") (pin "6") (pinfunction "6_6") (pintype "passive"))
      (node (ref "P3") (pin "8") (pinfunction "8_8") (pintype "passive"))
      (node (ref "P4") (pin "1") (pinfunction "+5V_1") (pintype "power_in"))
      (node (ref "P5") (pin "1") (pinfunction "+5V_1") (pintype "power_in"))
    )
    (net (code "107") (name "GND") (class "Default")
      (node (ref "C1") (pin "2") (pinfunction "2_2") (pintype "passive"))
      (node (ref "C10") (pin "1") (pinfunction "1_1") (pintype "passive"))
      (node (ref "C11") (pin "2") (pinfunction "2_2") (pintype "passive"))
      (node (ref "C12") (pin "1") (pinfunction "1_1") (pintype "passive"))
      (node (ref "C13") (pin "2") (pinfunction "2_2") (pintype "passive"))
      (node (ref "C14") (pin "1") (pinfunction "1_1") (pintype "passive"))
      (node (ref "C2") (pin "2") (pinfunction "2_2") (pintype "passive"))
      (node (ref "C3") (pin "2") (pinfunction "2_2") (pintype "passive"))
      (node (ref "C4") (pin "1") (pinfunction "1_1") (pintype "passive"))
      (node (ref "C42") (pin "1") (pinfunction "1_1") (pintype "passive"))
      (node (ref "C45") (pin "2") (pinfunction "2_2") (pintype "passive"))
      (node (ref "C46") (pin "2") (pinfunction "2_2") (pintype "passive"))
      (node (ref "C47") (pin "1") (pinfunction "1_1") (pintype "passive"))
      (node (ref "C5") (pin "2") (pinfunction "2_2") (pintype "passive"))
      (node (ref "C6") (pin "2") (pinfunction "2_2") (pintype "passive"))
      (node (ref "C7") (pin "1") (pinfunction "1_1") (pintype "passive"))
      (node (ref "C8") (pin "1") (pinfunction "1_1") (pintype "passive"))
      (node (ref "C9") (pin "1") (pinfunction "1_1") (pintype "passive"))
      (node (ref "P1") (pin "2") (pinfunction "2_2") (pintype "passive"))
      (node (ref "P10") (pin "5") (pinfunction "5_5") (pintype "passive"))
      (node (ref "P10") (pin "6") (pinfunction "6_6") (pintype "passive"))
      (node (ref "P14") (pin "A1") (pinfunction "GND_A1") (pintype "bidirectional"))
      (node (ref "P14") (pin "B1") (pinfunction "GND_B1") (pintype "bidirectional"))
      (node (ref "P15") (pin "A1") (pinfunction "GND_A1") (pintype "bidirectional"))
      (node (ref "P15") (pin "B1") (pinfunction "GND_B1") (pintype "bidirectional"))
      (node (ref "P2") (pin "8") (pintype "passive"))
      (node (ref "P3") (pin "1") (pinfunction "1_1") (pintype "passive"))
      (node (ref "P3") (pin "11") (pinfunction "11_11") (pintype "passive"))
      (node (ref "P3") (pin "13") (pinfunction "13_13") (pintype "passive"))
      (node (ref "P3") (pin "15") (pinfunction "15_15") (pintype "passive"))
      (node (ref "P3") (pin "2") (pinfunction "2_2") (pintype "passive"))
      (node (ref "P3") (pin "3") (pinfunction "3_3") (pintype "passive"))
      (node (ref "P3") (pin "4") (pinfunction "4_4") (pintype "passive"))
      (node (ref "P3") (pin "5") (pinfunction "5_5") (pintype "passive"))
      (node (ref "P3") (pin "7") (pinfunction "7_7") (pintype "passive"))
      (node (ref "P3") (pin "9") (pinfunction "9_9") (pintype "passive"))
      (node (ref "P4") (pin "4") (pinfunction "GND_4") (pintype "power_in"))
      (node (ref "P4") (pin "5") (pinfunction "GND_5") (pintype "power_in"))
      (node (ref "P4") (pin "6") (pinfunction "GND_6") (pintype "power_in"))
      (node (ref "P5") (pin "4") (pinfunction "GND_4") (pintype "power_in"))
      (node (ref "P5") (pin "5") (pinfunction "GND_5") (pintype "power_in"))
      (node (ref "P5") (pin "6") (pinfunction "GND_6") (pintype "power_in"))
      (node (ref "P6") (pin "25") (pinfunction "25_25") (pintype "passive"))
      (node (ref "P6") (pin "26") (pinfunction "26_26") (pintype "passive"))
      (node (ref "P6") (pin "27") (pinfunction "27_27") (pintype "passive"))
      (node (ref "P6") (pin "28") (pinfunction "28_28") (pintype "passive"))
      (node (ref "P6") (pin "5") (pinfunction "5_5") (pintype "passive"))
      (node (ref "P7") (pin "6") (pinfunction "6_6") (pintype "passive"))
      (node (ref "P9") (pin "1") (pinfunction "1_1") (pintype "passive"))
      (node (ref "P9") (pin "2") (pinfunction "2_2") (pintype "passive"))
      (node (ref "P9") (pin "39") (pinfunction "39_39") (pintype "passive"))
      (node (ref "P9") (pin "40") (pinfunction "40_40") (pintype "passive"))
      (node (ref "P9") (pin "41") (pinfunction "41_41") (pintype "passive"))
      (node (ref "P9") (pin "42") (pinfunction "42_42") (pintype "passive"))
      (node (ref "R17") (pin "1") (pinfunction "1_1") (pintype "passive"))
      (node (ref "R21") (pin "2") (pinfunction "2_2") (pintype "passive"))
      (node (ref "R22") (pin "2") (pinfunction "2_2") (pintype "passive"))
      (node (ref "R23") (pin "2") (pinfunction "2_2") (pintype "passive"))
      (node (ref "R24") (pin "2") (pinfunction "2_2") (pintype "passive"))
      (node (ref "R25") (pin "2") (pinfunction "2_2") (pintype "passive"))
      (node (ref "R26") (pin "2") (pinfunction "2_2") (pintype "passive"))
      (node (ref "R3") (pin "2") (pintype "passive"))
      (node (ref "R5") (pin "1") (pintype "passive"))
      (node (ref "S3") (pin "1") (pinfunction "1_1") (pintype "passive"))
      (node (ref "U1") (pin "1") (pinfunction "GND_1") (pintype "passive"))
      (node (ref "U2") (pin "10") (pinfunction "VSS_5_10") (pintype "power_in"))
      (node (ref "U2") (pin "19") (pinfunction "VSSA_19") (pintype "power_in"))
      (node (ref "U2") (pin "27") (pinfunction "VSS_4_27") (pintype "power_in"))
      (node (ref "U2") (pin "49") (pinfunction "VSS_1_49") (pintype "power_in"))
      (node (ref "U2") (pin "74") (pinfunction "VSS_2_74") (pintype "power_in"))
      (node (ref "U2") (pin "99") (pinfunction "VSS_3_99") (pintype "power_in"))
    )
    (net (code "108") (name "Net-(D1-K)") (class "Default")
      (node (ref "D1") (pin "2") (pinfunction "K_2") (pintype "passive"))
      (node (ref "R3") (pin "1") (pintype "passive"))
    )
    (net (code "109") (name "Net-(D3-A)") (class "Default")
      (node (ref "D3") (pin "1") (pinfunction "A_1") (pintype "passive"))
      (node (ref "R1") (pin "2") (pintype "passive"))
    )
    (net (code "110") (name "Net-(D4-A)") (class "Default")
      (node (ref "D4") (pin "1") (pinfunction "A_1") (pintype "passive"))
      (node (ref "R4") (pin "2") (pintype "passive"))
    )
    (net (code "111") (name "Net-(P2-Pad9)") (class "Default")
      (node (ref "P2") (pin "9") (pintype "passive"))
      (node (ref "R8") (pin "2") (pintype "passive"))
    )
    (net (code "112") (name "Net-(P2-Pad12)") (class "Default")
      (node (ref "P2") (pin "12") (pintype "passive"))
      (node (ref "R9") (pin "2") (pintype "passive"))
    )
    (net (code "113") (name "Net-(P14-CC-PadA5)") (class "Default")
      (node (ref "P14") (pin "A5") (pinfunction "CC_A5") (pintype "bidirectional"))
      (node (ref "R25") (pin "1") (pinfunction "1_1") (pintype "passive"))
    )
    (net (code "114") (name "Net-(P14-CC-PadB5)") (class "Default")
      (node (ref "P14") (pin "B5") (pinfunction "CC_B5") (pintype "bidirectional"))
      (node (ref "R26") (pin "1") (pinfunction "1_1") (pintype "passive"))
    )
    (net (code "115") (name "Net-(P15-CC-PadA5)") (class "Default")
      (node (ref "P15") (pin "A5") (pinfunction "CC_A5") (pintype "bidirectional"))
      (node (ref "R23") (pin "1") (pinfunction "1_1") (pintype "passive"))
    )
    (net (code "116") (name "Net-(P15-CC-PadB5)") (class "Default")
      (node (ref "P15") (pin "B5") (pinfunction "CC_B5") (pintype "bidirectional"))
      (node (ref "R24") (pin "1") (pinfunction "1_1") (pintype "passive"))
    )
    (net (code "117") (name "Net-(R5-Pad2)") (class "Default")
      (node (ref "R5") (pin "2") (pintype "passive"))
      (node (ref "S2") (pin "2") (pinfunction "2_2") (pintype "passive"))
    )
    (net (code "118") (name "Net-(R20-Pad2)") (class "Default")
      (node (ref "R20") (pin "2") (pinfunction "2_2") (pintype "passive"))
      (node (ref "S4") (pin "2") (pinfunction "2_2") (pintype "passive"))
    )
    (net (code "119") (name "Net-(S1-COMMON)") (class "Default")
      (node (ref "F1") (pin "2") (pinfunction "2_2") (pintype "passive"))
      (node (ref "S1") (pin "1") (pinfunction "COMMON_1") (pintype "passive"))
    )
    (net (code "120") (name "Net-(S1-NC)") (class "Default")
      (node (ref "C1") (pin "1") (pinfunction "1_1") (pintype "passive"))
      (node (ref "S1") (pin "2") (pinfunction "NC_2") (pintype "passive"))
      (node (ref "U1") (pin "3") (pinfunction "Vin_3") (pintype "passive"))
    )
    (net (code "121") (name "Net-(U2-VIO_3)") (class "Default")
      (node (ref "C42") (pin "2") (pinfunction "2_2") (pintype "passive"))
      (node (ref "U2") (pin "100") (pinfunction "VIO_3_100") (pintype "power_in"))
    )
    (net (code "122") (name "unconnected-(P2-Pad7)") (class "Default")
      (node (ref "P2") (pin "7") (pintype "passive"))
    )
    (net (code "123") (name "unconnected-(P14-RFU1-PadA8)") (class "Default")
      (node (ref "P14") (pin "A8") (pinfunction "RFU1_A8") (pintype "bidirectional+no_connect"))
    )
    (net (code "124") (name "unconnected-(P14-RFU1-PadB8)") (class "Default")
      (node (ref "P14") (pin "B8") (pinfunction "RFU1_B8") (pintype "bidirectional+no_connect"))
    )
    (net (code "125") (name "unconnected-(P15-RFU1-PadA8)") (class "Default")
      (node (ref "P15") (pin "A8") (pinfunction "RFU1_A8") (pintype "bidirectional+no_connect"))
    )
    (net (code "126") (name "unconnected-(P15-RFU1-PadB8)") (class "Default")
      (node (ref "P15") (pin "B8") (pinfunction "RFU1_B8") (pintype "bidirectional+no_connect"))
    )
    (net (code "127") (name "unconnected-(S1-NO-Pad3)") (class "Default")
      (node (ref "S1") (pin "3") (pinfunction "NO_3") (pintype "passive"))
    )
    (net (code "128") (name "unconnected-(U2-PB5-Pad91)") (class "Default")
      (node (ref "U2") (pin "91") (pinfunction "PB5_91") (pintype "bidirectional"))
    )
  )
)
